# ClockTamerMotherboard.net
KiCad netlist of a schematic drawn in Altium Designer
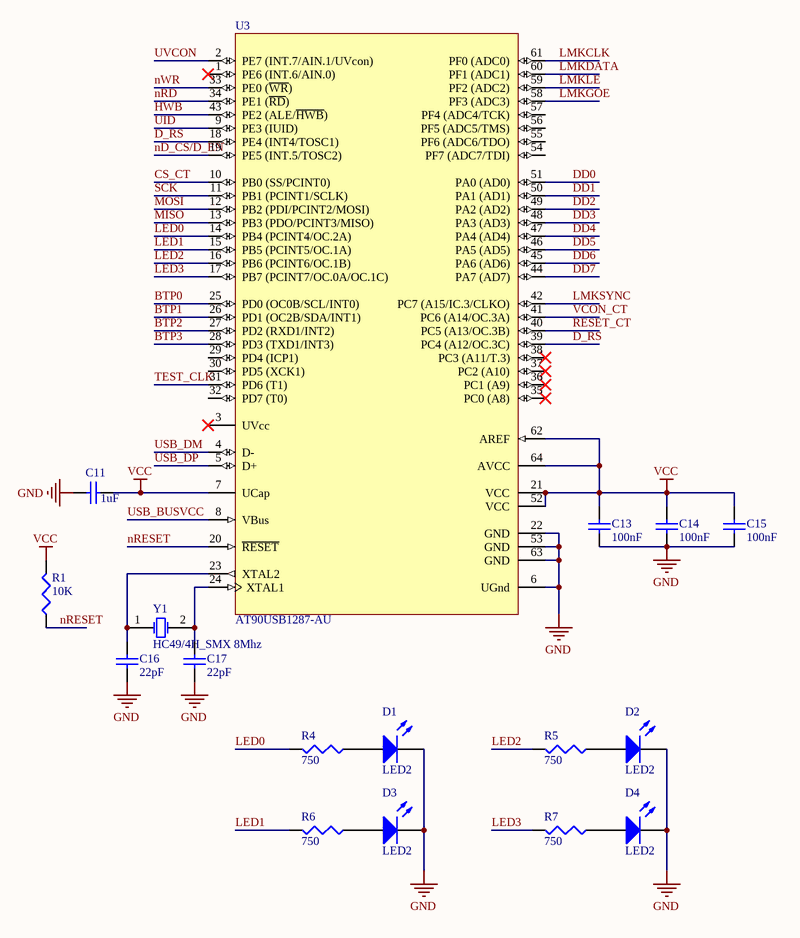
[diagram p0: ClockTamerMotherboard.SchDoc]

(export (version "E")
  (design (tool "Eeschema 10.0.6"))
  (components
    (comp (ref "C11")
      (value "1uF")
      (footprint "1608[0603]")
      (description "Capacitor (Semiconductor SIM Model)")
      (fields (field (name "PUBLISHER") "Altium Limited"))
      (libsource (lib "Miscellaneous Devices") (part "Cap Semi"))
    )
    (comp (ref "C13")
      (value "100nF")
      (footprint "1608[0603]")
      (description "Capacitor (Semiconductor SIM Model)")
      (fields (field (name "PUBLISHER") "Altium Limited"))
      (libsource (lib "Miscellaneous Devices") (part "Cap Semi"))
    )
    (comp (ref "C14")
      (value "100nF")
      (footprint "1608[0603]")
      (description "Capacitor (Semiconductor SIM Model)")
      (fields (field (name "PUBLISHER") "Altium Limited"))
      (libsource (lib "Miscellaneous Devices") (part "Cap Semi"))
    )
    (comp (ref "C15")
      (value "100nF")
      (footprint "1608[0603]")
      (description "Capacitor (Semiconductor SIM Model)")
      (fields (field (name "PUBLISHER") "Altium Limited"))
      (libsource (lib "Miscellaneous Devices") (part "Cap Semi"))
    )
    (comp (ref "C16")
      (value "22pF")
      (footprint "1608[0603]")
      (description "Capacitor (Semiconductor SIM Model)")
      (fields (field (name "PUBLISHER") "Altium Limited"))
      (libsource (lib "Miscellaneous Devices") (part "Cap Semi"))
    )
    (comp (ref "C17")
      (value "22pF")
      (footprint "1608[0603]")
      (description "Capacitor (Semiconductor SIM Model)")
      (fields (field (name "PUBLISHER") "Altium Limited"))
      (libsource (lib "Miscellaneous Devices") (part "Cap Semi"))
    )
    (comp (ref "D1")
      (value "LED2")
      (footprint "3.2X1.6X1.1")
      (description "Typical RED, GREEN, YELLOW, AMBER GaAs LED")
      (fields (field (name "PUBLISHER") "Altium Limited"))
      (libsource (lib "Miscellaneous Devices") (part "LED2"))
    )
    (comp (ref "D2")
      (value "LED2")
      (footprint "3.2X1.6X1.1")
      (description "Typical RED, GREEN, YELLOW, AMBER GaAs LED")
      (fields (field (name "PUBLISHER") "Altium Limited"))
      (libsource (lib "Miscellaneous Devices") (part "LED2"))
    )
    (comp (ref "D3")
      (value "LED2")
      (footprint "3.2X1.6X1.1")
      (description "Typical RED, GREEN, YELLOW, AMBER GaAs LED")
      (fields (field (name "PUBLISHER") "Altium Limited"))
      (libsource (lib "Miscellaneous Devices") (part "LED2"))
    )
    (comp (ref "D4")
      (value "LED2")
      (footprint "3.2X1.6X1.1")
      (description "Typical RED, GREEN, YELLOW, AMBER GaAs LED")
      (fields (field (name "PUBLISHER") "Altium Limited"))
      (libsource (lib "Miscellaneous Devices") (part "LED2"))
    )
    (comp (ref "R1")
      (value "10K")
      (footprint "J1-0603")
      (description "Resistor")
      (fields (field (name "PUBLISHER") "Altium Limited"))
      (libsource (lib "Miscellaneous Devices") (part "Res3"))
    )
    (comp (ref "R4")
      (value "750")
      (footprint "J1-0603")
      (description "Resistor")
      (fields (field (name "PUBLISHER") "Altium Limited"))
      (libsource (lib "Miscellaneous Devices") (part "Res3"))
    )
    (comp (ref "R5")
      (value "750")
      (footprint "J1-0603")
      (description "Resistor")
      (fields (field (name "PUBLISHER") "Altium Limited"))
      (libsource (lib "Miscellaneous Devices") (part "Res3"))
    )
    (comp (ref "R6")
      (value "750")
      (footprint "J1-0603")
      (description "Resistor")
      (fields (field (name "PUBLISHER") "Altium Limited"))
      (libsource (lib "Miscellaneous Devices") (part "Res3"))
    )
    (comp (ref "R7")
      (value "750")
      (footprint "J1-0603")
      (description "Resistor")
      (fields (field (name "PUBLISHER") "Altium Limited"))
      (libsource (lib "Miscellaneous Devices") (part "Res3"))
    )
    (comp (ref "U3")
      (value "AT90USB1287-AU")
      (footprint "64MD_N")
      (fields (field (name "PUBLISHER") "Altium Limited"))
      (libsource (lib "Atmel Microcontroller 8-Bit megaAVR") (part "AT90USB1287-AU"))
    )
    (comp (ref "Y1")
      (value "HC49/4H_SMX 8Mhz")
      (footprint "HC49/4H_SMX")
      (description "Surface Mount Quartz Crystal")
      (fields (field (name "PUBLISHER") "Altium Limited"))
      (libsource (lib "C-MAC Crystal Oscillator") (part "HC49/4H_SMX"))
    )
  )
  (nets
    (net (code "1") (name "/BTP0") (class "Default")
      (node (ref "U3") (pin "25") (pinfunction "PD0_(OC0B/SCL/INT0)_25") (pintype "bidirectional"))
    )
    (net (code "2") (name "/BTP1") (class "Default")
      (node (ref "U3") (pin "26") (pinfunction "PD1_(OC2B/SDA/INT1)_26") (pintype "bidirectional"))
    )
    (net (code "3") (name "/BTP2") (class "Default")
      (node (ref "U3") (pin "27") (pinfunction "PD2_(RXD1/INT2)_27") (pintype "bidirectional"))
    )
    (net (code "4") (name "/BTP3") (class "Default")
      (node (ref "U3") (pin "28") (pinfunction "PD3_(TXD1/INT3)_28") (pintype "bidirectional"))
    )
    (net (code "5") (name "/CS_CT") (class "Default")
      (node (ref "U3") (pin "10") (pinfunction "PB0_(SS/PCINT0)_10") (pintype "bidirectional"))
    )
    (net (code "6") (name "/DD0") (class "Default")
      (node (ref "U3") (pin "51") (pinfunction "PA0_(AD0)_51") (pintype "bidirectional"))
    )
    (net (code "7") (name "/DD1") (class "Default")
      (node (ref "U3") (pin "50") (pinfunction "PA1_(AD1)_50") (pintype "bidirectional"))
    )
    (net (code "8") (name "/DD2") (class "Default")
      (node (ref "U3") (pin "49") (pinfunction "PA2_(AD2)_49") (pintype "bidirectional"))
    )
    (net (code "9") (name "/DD3") (class "Default")
      (node (ref "U3") (pin "48") (pinfunction "PA3_(AD3)_48") (pintype "bidirectional"))
    )
    (net (code "10") (name "/DD4") (class "Default")
      (node (ref "U3") (pin "47") (pinfunction "PA4_(AD4)_47") (pintype "bidirectional"))
    )
    (net (code "11") (name "/DD5") (class "Default")
      (node (ref "U3") (pin "46") (pinfunction "PA5_(AD5)_46") (pintype "bidirectional"))
    )
    (net (code "12") (name "/DD6") (class "Default")
      (node (ref "U3") (pin "45") (pinfunction "PA6_(AD6)_45") (pintype "bidirectional"))
    )
    (net (code "13") (name "/DD7") (class "Default")
      (node (ref "U3") (pin "44") (pinfunction "PA7_(AD7)_44") (pintype "bidirectional"))
    )
    (net (code "14") (name "/D_RS") (class "Default")
      (node (ref "U3") (pin "18") (pinfunction "PE4_(INT4/TOSC1)_18") (pintype "bidirectional"))
      (node (ref "U3") (pin "39") (pinfunction "PC4_(A12/OC.3C)_39") (pintype "bidirectional"))
    )
    (net (code "15") (name "/HWB") (class "Default")
      (node (ref "U3") (pin "43") (pinfunction "PE2_(ALE/~{HWB})_43") (pintype "bidirectional"))
    )
    (net (code "16") (name "/LED0") (class "Default")
      (node (ref "R4") (pin "2") (pinfunction "2_2") (pintype "passive"))
      (node (ref "U3") (pin "14") (pinfunction "PB4_(PCINT4/OC.2A)_14") (pintype "bidirectional"))
    )
    (net (code "17") (name "/LED1") (class "Default")
      (node (ref "R6") (pin "2") (pinfunction "2_2") (pintype "passive"))
      (node (ref "U3") (pin "15") (pinfunction "PB5_(PCINT5/OC.1A)_15") (pintype "bidirectional"))
    )
    (net (code "18") (name "/LED2") (class "Default")
      (node (ref "R5") (pin "2") (pinfunction "2_2") (pintype "passive"))
      (node (ref "U3") (pin "16") (pinfunction "PB6_(PCINT6/OC.1B)_16") (pintype "bidirectional"))
    )
    (net (code "19") (name "/LED3") (class "Default")
      (node (ref "R7") (pin "2") (pinfunction "2_2") (pintype "passive"))
      (node (ref "U3") (pin "17") (pinfunction "PB7_(PCINT7/OC.0A/OC.1C)_17") (pintype "bidirectional"))
    )
    (net (code "20") (name "/LMKCLK") (class "Default")
      (node (ref "U3") (pin "61") (pinfunction "PF0_(ADC0)_61") (pintype "bidirectional"))
    )
    (net (code "21") (name "/LMKDATA") (class "Default")
      (node (ref "U3") (pin "60") (pinfunction "PF1_(ADC1)_60") (pintype "bidirectional"))
    )
    (net (code "22") (name "/LMKGOE") (class "Default")
      (node (ref "U3") (pin "58") (pinfunction "PF3_(ADC3)_58") (pintype "bidirectional"))
    )
    (net (code "23") (name "/LMKLE") (class "Default")
      (node (ref "U3") (pin "59") (pinfunction "PF2_(ADC2)_59") (pintype "bidirectional"))
    )
    (net (code "24") (name "/LMKSYNC") (class "Default")
      (node (ref "U3") (pin "42") (pinfunction "PC7_(A15/IC.3/CLKO)_42") (pintype "bidirectional"))
    )
    (net (code "25") (name "/MISO") (class "Default")
      (node (ref "U3") (pin "13") (pinfunction "PB3_(PDO/PCINT3/MISO)_13") (pintype "bidirectional"))
    )
    (net (code "26") (name "/MOSI") (class "Default")
      (node (ref "U3") (pin "12") (pinfunction "PB2_(PDI/PCINT2/MOSI)_12") (pintype "bidirectional"))
    )
    (net (code "27") (name "/RESET_CT") (class "Default")
      (node (ref "U3") (pin "40") (pinfunction "PC5_(A13/OC.3B)_40") (pintype "bidirectional"))
    )
    (net (code "28") (name "/SCK") (class "Default")
      (node (ref "U3") (pin "11") (pinfunction "PB1_(PCINT1/SCLK)_11") (pintype "bidirectional"))
    )
    (net (code "29") (name "/TEST_CLK") (class "Default")
      (node (ref "U3") (pin "31") (pinfunction "PD6_(T1)_31") (pintype "bidirectional"))
    )
    (net (code "30") (name "/UID") (class "Default")
      (node (ref "U3") (pin "9") (pinfunction "PE3_(IUID)_9") (pintype "bidirectional"))
    )
    (net (code "31") (name "/USB_BUSVCC") (class "Default")
      (node (ref "U3") (pin "8") (pinfunction "VBus_8") (pintype "input"))
    )
    (net (code "32") (name "/USB_DM") (class "Default")
      (node (ref "U3") (pin "4") (pinfunction "D-_4") (pintype "bidirectional"))
    )
    (net (code "33") (name "/USB_DP") (class "Default")
      (node (ref "U3") (pin "5") (pinfunction "D+_5") (pintype "bidirectional"))
    )
    (net (code "34") (name "/UVCON") (class "Default")
      (node (ref "U3") (pin "2") (pinfunction "PE7_(INT.7/AIN.1/UVcon)_2") (pintype "bidirectional"))
    )
    (net (code "35") (name "/VCON_CT") (class "Default")
      (node (ref "U3") (pin "41") (pinfunction "PC6_(A14/OC.3A)_41") (pintype "bidirectional"))
    )
    (net (code "36") (name "/nD_CS{slash}D_EN") (class "Default")
      (node (ref "U3") (pin "19") (pinfunction "PE5_(INT.5/TOSC2)_19") (pintype "bidirectional"))
    )
    (net (code "37") (name "/nRD") (class "Default")
      (node (ref "U3") (pin "34") (pinfunction "PE1_(~{RD})_34") (pintype "bidirectional"))
    )
    (net (code "38") (name "/nRESET") (class "Default")
      (node (ref "R1") (pin "1") (pinfunction "1_1") (pintype "passive"))
      (node (ref "U3") (pin "20") (pinfunction "~{RESET}_20") (pintype "input"))
    )
    (net (code "39") (name "/nWR") (class "Default")
      (node (ref "U3") (pin "33") (pinfunction "PE0_(~{WR})_33") (pintype "bidirectional"))
    )
    (net (code "40") (name "GND") (class "Default")
      (node (ref "C11") (pin "1") (pinfunction "1_1") (pintype "passive"))
      (node (ref "C13") (pin "2") (pinfunction "2_2") (pintype "passive"))
      (node (ref "C14") (pin "1") (pinfunction "1_1") (pintype "passive"))
      (node (ref "C15") (pin "1") (pinfunction "1_1") (pintype "passive"))
      (node (ref "C16") (pin "1") (pinfunction "1_1") (pintype "passive"))
      (node (ref "C17") (pin "1") (pinfunction "1_1") (pintype "passive"))
      (node (ref "D1") (pin "2") (pinfunction "K_2") (pintype "passive"))
      (node (ref "D2") (pin "2") (pinfunction "K_2") (pintype "passive"))
      (node (ref "D3") (pin "2") (pinfunction "K_2") (pintype "passive"))
      (node (ref "D4") (pin "2") (pinfunction "K_2") (pintype "passive"))
      (node (ref "U3") (pin "22") (pinfunction "GND_22") (pintype "power_in"))
      (node (ref "U3") (pin "53") (pinfunction "GND_53") (pintype "power_in"))
      (node (ref "U3") (pin "6") (pinfunction "UGnd_6") (pintype "power_in"))
      (node (ref "U3") (pin "63") (pinfunction "GND_63") (pintype "power_in"))
    )
    (net (code "41") (name "Net-(D1-A)") (class "Default")
      (node (ref "D1") (pin "1") (pinfunction "A_1") (pintype "passive"))
      (node (ref "R4") (pin "1") (pinfunction "1_1") (pintype "passive"))
    )
    (net (code "42") (name "Net-(D2-A)") (class "Default")
      (node (ref "D2") (pin "1") (pinfunction "A_1") (pintype "passive"))
      (node (ref "R5") (pin "1") (pinfunction "1_1") (pintype "passive"))
    )
    (net (code "43") (name "Net-(D3-A)") (class "Default")
      (node (ref "D3") (pin "1") (pinfunction "A_1") (pintype "passive"))
      (node (ref "R6") (pin "1") (pinfunction "1_1") (pintype "passive"))
    )
    (net (code "44") (name "Net-(D4-A)") (class "Default")
      (node (ref "D4") (pin "1") (pinfunction "A_1") (pintype "passive"))
      (node (ref "R7") (pin "1") (pinfunction "1_1") (pintype "passive"))
    )
    (net (code "45") (name "Net-(U3-XTAL1)") (class "Default")
      (node (ref "C17") (pin "2") (pinfunction "2_2") (pintype "passive"))
      (node (ref "U3") (pin "24") (pinfunction "XTAL1_24") (pintype "input"))
      (node (ref "Y1") (pin "2") (pinfunction "OSC2_2") (pintype "passive"))
    )
    (net (code "46") (name "Net-(U3-XTAL2)") (class "Default")
      (node (ref "C16") (pin "2") (pinfunction "2_2") (pintype "passive"))
      (node (ref "U3") (pin "23") (pinfunction "XTAL2_23") (pintype "output"))
      (node (ref "Y1") (pin "1") (pinfunction "OSC1_1") (pintype "passive"))
    )
    (net (code "47") (name "VCC") (class "Default")
      (node (ref "C11") (pin "2") (pinfunction "2_2") (pintype "passive"))
      (node (ref "C13") (pin "1") (pinfunction "1_1") (pintype "passive"))
      (node (ref "C14") (pin "2") (pinfunction "2_2") (pintype "passive"))
      (node (ref "C15") (pin "2") (pinfunction "2_2") (pintype "passive"))
      (node (ref "R1") (pin "2") (pinfunction "2_2") (pintype "passive"))
      (node (ref "U3") (pin "21") (pinfunction "VCC_21") (pintype "power_in"))
      (node (ref "U3") (pin "52") (pinfunction "VCC_52") (pintype "power_in"))
      (node (ref "U3") (pin "62") (pinfunction "AREF_62") (pintype "input"))
      (node (ref "U3") (pin "64") (pinfunction "AVCC_64") (pintype "power_in"))
      (node (ref "U3") (pin "7") (pinfunction "UCap_7") (pintype "power_in"))
    )
    (net (code "48") (name "unconnected-(U3-PC0_(A8)-Pad35)") (class "Default")
      (node (ref "U3") (pin "35") (pinfunction "PC0_(A8)_35") (pintype "bidirectional+no_connect"))
    )
    (net (code "49") (name "unconnected-(U3-PC1_(A9)-Pad36)") (class "Default")
      (node (ref "U3") (pin "36") (pinfunction "PC1_(A9)_36") (pintype "bidirectional+no_connect"))
    )
    (net (code "50") (name "unconnected-(U3-PC2_(A10)-Pad37)") (class "Default")
      (node (ref "U3") (pin "37") (pinfunction "PC2_(A10)_37") (pintype "bidirectional+no_connect"))
    )
    (net (code "51") (name "unconnected-(U3-PC3_(A11{slash}T.3)-Pad38)") (class "Default")
      (node (ref "U3") (pin "38") (pinfunction "PC3_(A11/T.3)_38") (pintype "bidirectional+no_connect"))
    )
    (net (code "52") (name "unconnected-(U3-PD4_(ICP1)-Pad29)") (class "Default")
      (node (ref "U3") (pin "29") (pinfunction "PD4_(ICP1)_29") (pintype "bidirectional"))
    )
    (net (code "53") (name "unconnected-(U3-PD5_(XCK1)-Pad30)") (class "Default")
      (node (ref "U3") (pin "30") (pinfunction "PD5_(XCK1)_30") (pintype "bidirectional"))
    )
    (net (code "54") (name "unconnected-(U3-PD7_(T0)-Pad32)") (class "Default")
      (node (ref "U3") (pin "32") (pinfunction "PD7_(T0)_32") (pintype "bidirectional"))
    )
    (net (code "55") (name "unconnected-(U3-PE6_(INT.6{slash}AIN.0)-Pad1)") (class "Default")
      (node (ref "U3") (pin "1") (pinfunction "PE6_(INT.6/AIN.0)_1") (pintype "bidirectional+no_connect"))
    )
    (net (code "56") (name "unconnected-(U3-PF4_(ADC4{slash}TCK)-Pad57)") (class "Default")
      (node (ref "U3") (pin "57") (pinfunction "PF4_(ADC4/TCK)_57") (pintype "bidirectional"))
    )
    (net (code "57") (name "unconnected-(U3-PF5_(ADC5{slash}TMS)-Pad56)") (class "Default")
      (node (ref "U3") (pin "56") (pinfunction "PF5_(ADC5/TMS)_56") (pintype "bidirectional"))
    )
    (net (code "58") (name "unconnected-(U3-PF6_(ADC6{slash}TDO)-Pad55)") (class "Default")
      (node (ref "U3") (pin "55") (pinfunction "PF6_(ADC6/TDO)_55") (pintype "bidirectional"))
    )
    (net (code "59") (name "unconnected-(U3-PF7_(ADC7{slash}TDI)-Pad54)") (class "Default")
      (node (ref "U3") (pin "54") (pinfunction "PF7_(ADC7/TDI)_54") (pintype "bidirectional"))
    )
    (net (code "60") (name "unconnected-(U3-UVcc-Pad3)") (class "Default")
      (node (ref "U3") (pin "3") (pinfunction "UVcc_3") (pintype "power_in+no_connect"))
    )
  )
)
